# 03-USER_IO_STATUS.net
KiCad netlist of a schematic drawn in Altium Designer
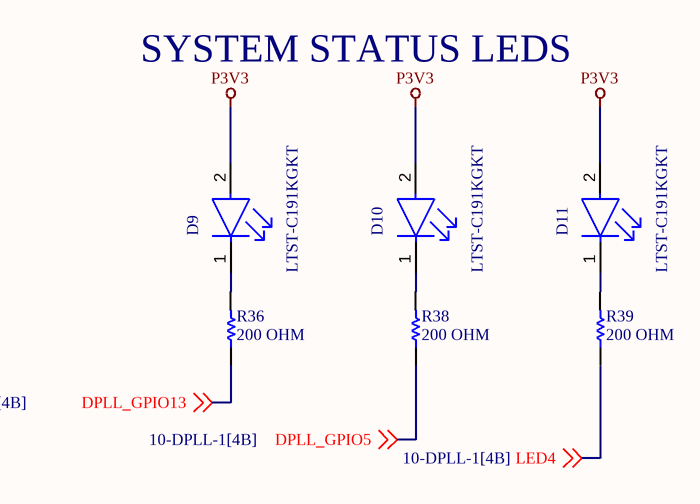
[diagram p0: 03-USER_IO_STATUS.SchDoc]

(export (version "E")
  (design (tool "Eeschema 10.0.6"))
  (components
    (comp (ref "D9")
      (value "LTST-C191KGKT")
      (footprint "FP-LTST-C191KGKT-MFG")
      (description "LED GREEN CLEAR SMD")
      (libsource (lib "Altium Content Vault") (part "8706943c75ba83719d021d2fdc84c58"))
    )
    (comp (ref "D10")
      (value "LTST-C191KGKT")
      (footprint "FP-LTST-C191KGKT-MFG")
      (description "LED GREEN CLEAR SMD")
      (libsource (lib "Altium Content Vault") (part "8706943c75ba83719d021d2fdc84c58"))
    )
    (comp (ref "D11")
      (value "LTST-C191KGKT")
      (footprint "FP-LTST-C191KGKT-MFG")
      (description "LED GREEN CLEAR SMD")
      (libsource (lib "Altium Content Vault") (part "8706943c75ba83719d021d2fdc84c58"))
    )
    (comp (ref "R36")
      (value "200 OHM")
      (footprint "RESC1608X55X30NL15T15")
      (description "ERJ-3EKF2000V")
      (fields (field (name "MANUFACTURER") "Panasonic"))
      (libsource (lib "Altium Content Vault") (part "RES"))
    )
    (comp (ref "R38")
      (value "200 OHM")
      (footprint "RESC1608X55X30NL15T15")
      (description "ERJ-3EKF2000V")
      (fields (field (name "MANUFACTURER") "Panasonic"))
      (libsource (lib "Altium Content Vault") (part "RES"))
    )
    (comp (ref "R39")
      (value "200 OHM")
      (footprint "RESC1608X55X30NL15T15")
      (description "ERJ-3EKF2000V")
      (fields (field (name "MANUFACTURER") "Panasonic"))
      (libsource (lib "Altium Content Vault") (part "RES"))
    )
  )
  (nets
    (net (code "1") (name "DPLL_GPIO5") (class "Default")
      (node (ref "R38") (pin "1") (pinfunction "1_1") (pintype "passive"))
    )
    (net (code "2") (name "DPLL_GPIO13") (class "Default")
      (node (ref "R36") (pin "1") (pinfunction "1_1") (pintype "passive"))
    )
    (net (code "3") (name "LED4") (class "Default")
      (node (ref "R39") (pin "1") (pinfunction "1_1") (pintype "passive"))
    )
    (net (code "4") (name "Net-(D9-C)") (class "Default")
      (node (ref "D9") (pin "1") (pinfunction "C_1") (pintype "passive"))
      (node (ref "R36") (pin "2") (pinfunction "2_2") (pintype "passive"))
    )
    (net (code "5") (name "Net-(D10-C)") (class "Default")
      (node (ref "D10") (pin "1") (pinfunction "C_1") (pintype "passive"))
      (node (ref "R38") (pin "2") (pinfunction "2_2") (pintype "passive"))
    )
    (net (code "6") (name "Net-(D11-C)") (class "Default")
      (node (ref "D11") (pin "1") (pinfunction "C_1") (pintype "passive"))
      (node (ref "R39") (pin "2") (pinfunction "2_2") (pintype "passive"))
    )
    (net (code "7") (name "P3V3") (class "Default")
      (node (ref "D10") (pin "2") (pinfunction "A_2") (pintype "passive"))
      (node (ref "D11") (pin "2") (pinfunction "A_2") (pintype "passive"))
      (node (ref "D9") (pin "2") (pinfunction "A_2") (pintype "passive"))
    )
  )
)
